# quectel_mc60_breakout.net
KiCad netlist of a schematic drawn in Altium Designer
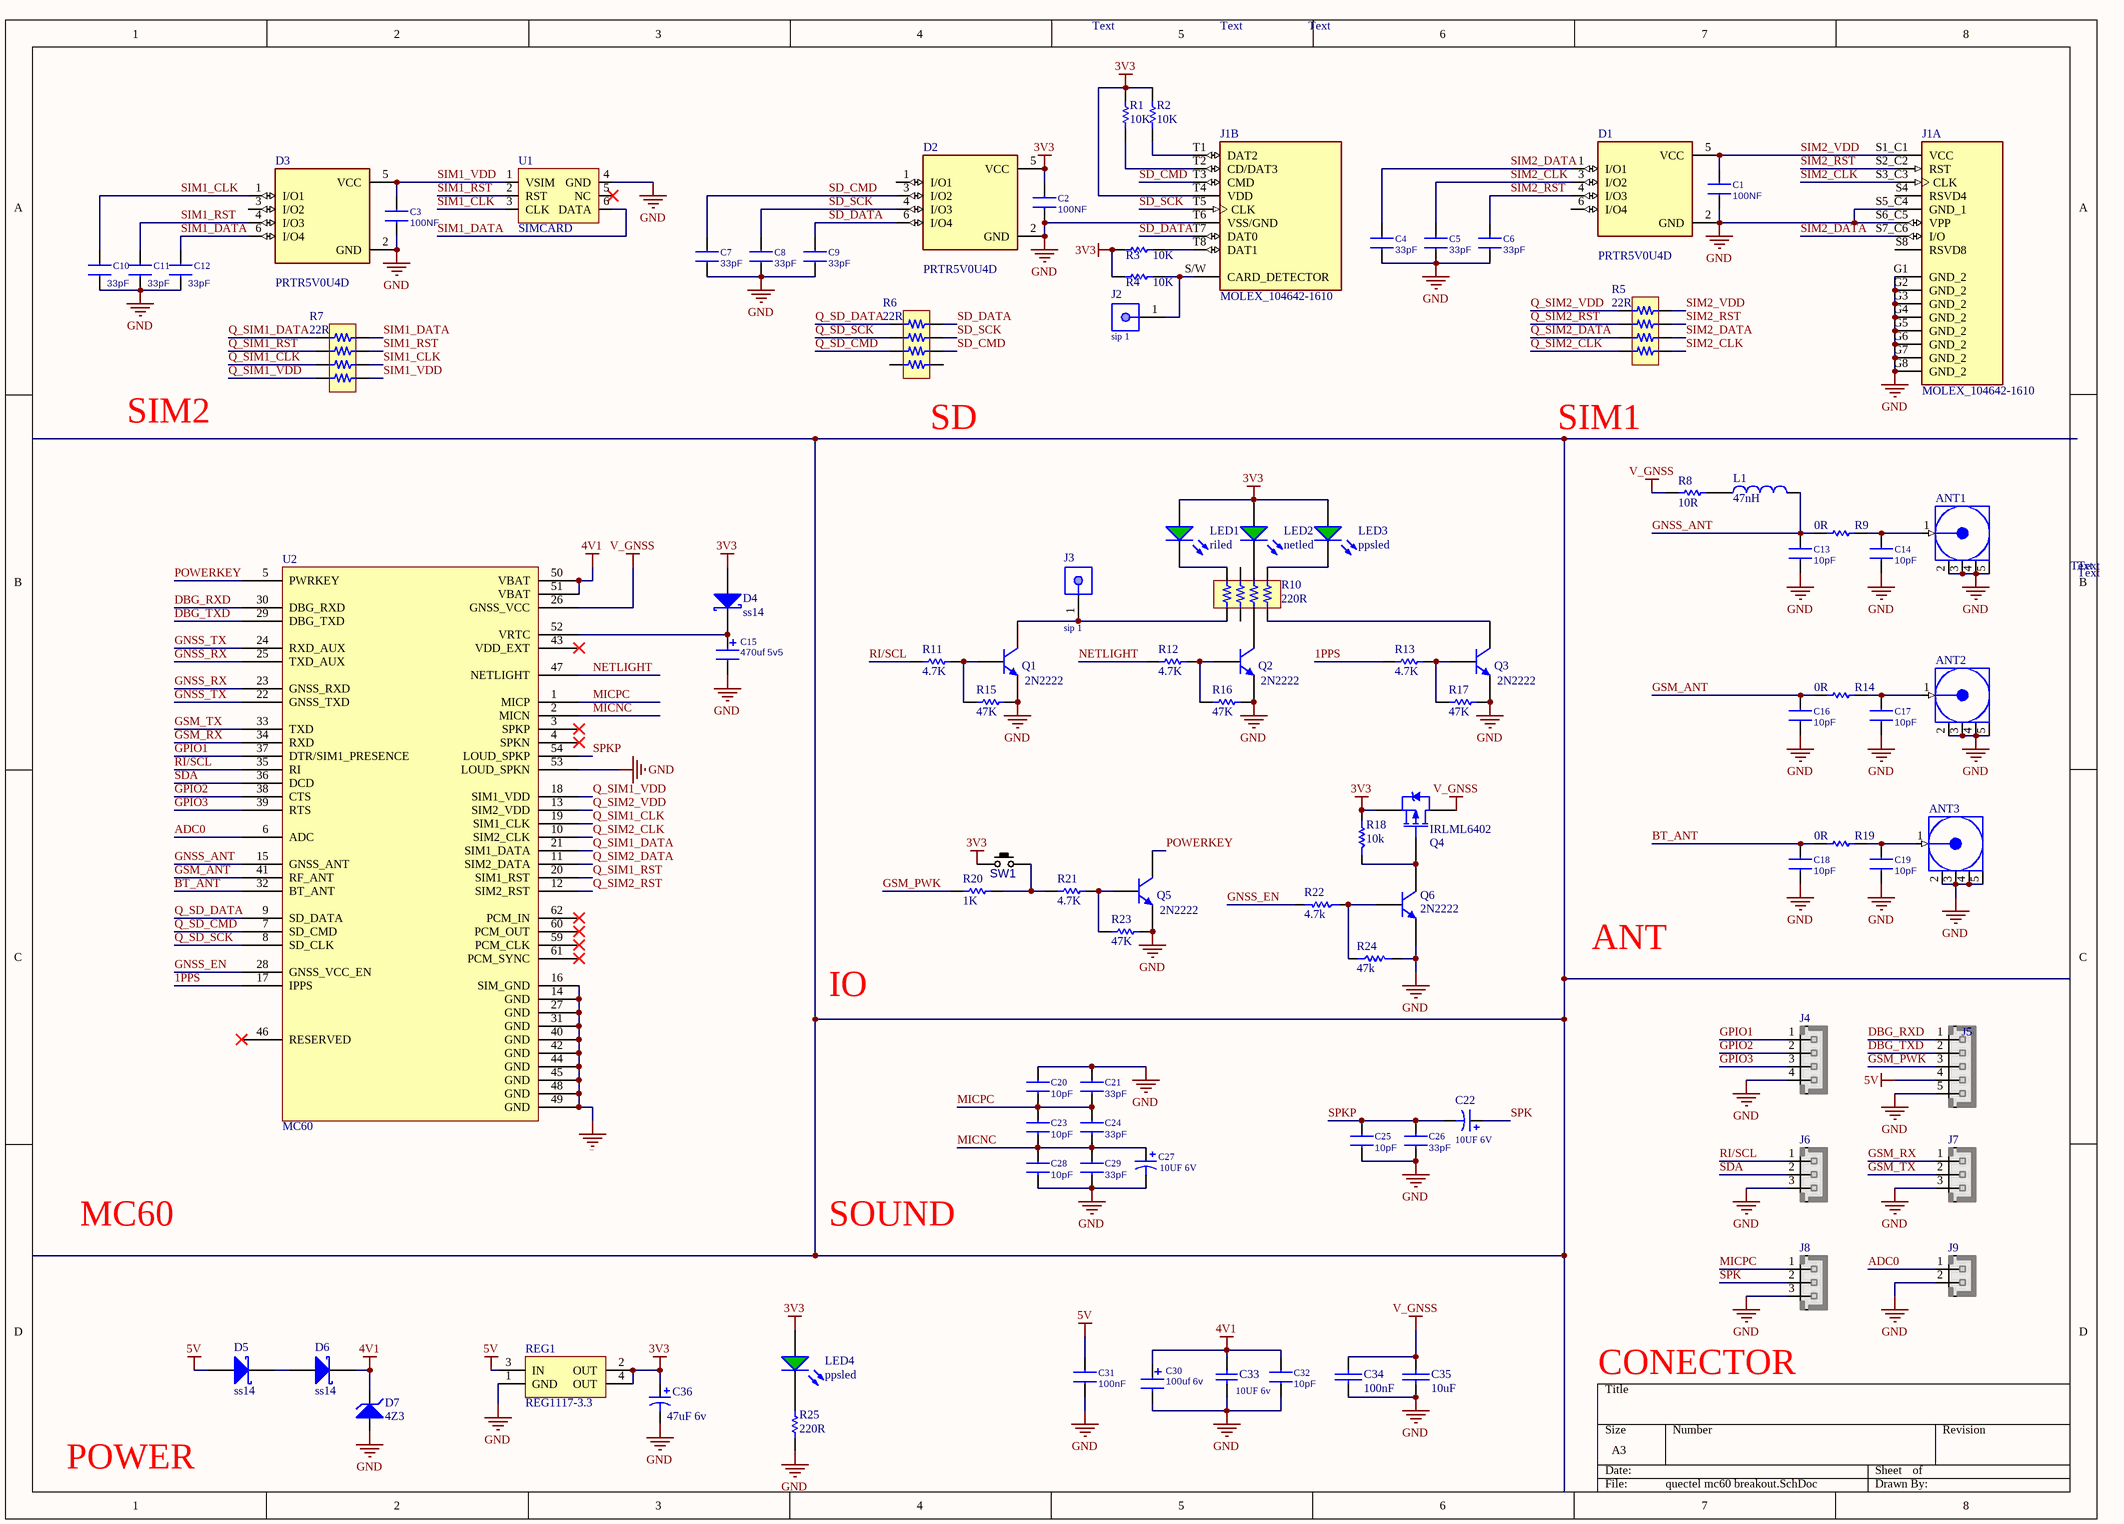
[diagram p0: quectel mc60 breakout.SchDoc]

(export (version "E")
  (design (tool "Eeschema 10.0.6"))
  (components
    (comp (ref "ANT1")
      (value "WR-SMA PCB Plug")
      (footprint "SMA-RA-6")
      (description "WR-SMA PCB Plug, THT, Right Angle")
      (fields (field (name "PART NUMBER") "60313002124523") (field (name "PUBLISHER") "Wurth Elektronik"))
      (libsource (lib "SMA") (part "WR-SMA PCB Plug"))
    )
    (comp (ref "ANT2")
      (value "WR-SMA PCB Plug")
      (footprint "SMA-RA-6")
      (description "WR-SMA PCB Plug, THT, Right Angle")
      (fields (field (name "PART NUMBER") "60313002124523") (field (name "PUBLISHER") "Wurth Elektronik"))
      (libsource (lib "SMA") (part "WR-SMA PCB Plug"))
    )
    (comp (ref "ANT3")
      (value "WR-SMA PCB Plug")
      (footprint "SMA-RA-6")
      (description "WR-SMA PCB Plug, THT, Right Angle")
      (fields (field (name "PART NUMBER") "60313002124523") (field (name "PUBLISHER") "Wurth Elektronik"))
      (libsource (lib "SMA") (part "WR-SMA PCB Plug"))
    )
    (comp (ref "C1")
      (value "100NF")
      (footprint "C0805E")
      (description "Capacitor")
      (libsource (lib "My_LIB") (part "Cap 1206"))
    )
    (comp (ref "C2")
      (value "100NF")
      (footprint "C0805E")
      (description "Capacitor")
      (libsource (lib "My_LIB") (part "Cap 1206"))
    )
    (comp (ref "C3")
      (value "100NF")
      (footprint "C0805E")
      (description "Capacitor")
      (libsource (lib "My_LIB") (part "Cap 1206"))
    )
    (comp (ref "C4")
      (value "33pF")
      (footprint "C0805E")
      (description "Capacitor")
      (libsource (lib "My_LIB") (part "Cap 1206"))
    )
    (comp (ref "C5")
      (value "33pF")
      (footprint "C0805E")
      (description "Capacitor")
      (libsource (lib "My_LIB") (part "Cap 1206"))
    )
    (comp (ref "C6")
      (value "33pF")
      (footprint "C0805E")
      (description "Capacitor")
      (libsource (lib "My_LIB") (part "Cap 1206"))
    )
    (comp (ref "C7")
      (value "33pF")
      (footprint "C0805E")
      (description "Capacitor")
      (libsource (lib "My_LIB") (part "Cap 1206"))
    )
    (comp (ref "C8")
      (value "33pF")
      (footprint "C0805E")
      (description "Capacitor")
      (libsource (lib "My_LIB") (part "Cap 1206"))
    )
    (comp (ref "C9")
      (value "33pF")
      (footprint "C0805E")
      (description "Capacitor")
      (libsource (lib "My_LIB") (part "Cap 1206"))
    )
    (comp (ref "C10")
      (value "33pF")
      (footprint "C0805E")
      (description "Capacitor")
      (libsource (lib "My_LIB") (part "Cap 1206"))
    )
    (comp (ref "C11")
      (value "33pF")
      (footprint "C0805E")
      (description "Capacitor")
      (libsource (lib "My_LIB") (part "Cap 1206"))
    )
    (comp (ref "C12")
      (value "33pF")
      (footprint "C0805E")
      (description "Capacitor")
      (libsource (lib "My_LIB") (part "Cap 1206"))
    )
    (comp (ref "C13")
      (value "10pF")
      (footprint "C0805E")
      (description "Capacitor")
      (libsource (lib "My_LIB") (part "Cap 1206"))
    )
    (comp (ref "C14")
      (value "10pF")
      (footprint "C0805E")
      (description "Capacitor")
      (libsource (lib "My_LIB") (part "Cap 1206"))
    )
    (comp (ref "C15")
      (value "470uf 5v5")
      (footprint "EEC S0HD473V")
      (description "Capacitor")
      (libsource (lib "My_LIB") (part "CPM3528"))
    )
    (comp (ref "C16")
      (value "10pF")
      (footprint "C0805E")
      (description "Capacitor")
      (libsource (lib "My_LIB") (part "Cap 1206"))
    )
    (comp (ref "C17")
      (value "10pF")
      (footprint "C0805E")
      (description "Capacitor")
      (libsource (lib "My_LIB") (part "Cap 1206"))
    )
    (comp (ref "C18")
      (value "10pF")
      (footprint "C0805E")
      (description "Capacitor")
      (libsource (lib "My_LIB") (part "Cap 1206"))
    )
    (comp (ref "C19")
      (value "10pF")
      (footprint "C0805E")
      (description "Capacitor")
      (libsource (lib "My_LIB") (part "Cap 1206"))
    )
    (comp (ref "C20")
      (value "10pF")
      (footprint "C0805E")
      (description "Capacitor")
      (libsource (lib "My_LIB") (part "Cap 1206"))
    )
    (comp (ref "C21")
      (value "33pF")
      (footprint "C0805E")
      (description "Capacitor")
      (libsource (lib "My_LIB") (part "Cap 1206"))
    )
    (comp (ref "C22")
      (value "10UF 6V")
      (footprint "C_TN_3216 (A)")
      (description "CAPASITOR ELECTRICAL DIP SMALL PACKAGE")
      (fields (field (name "PUBLISHER") "Altium Limited"))
      (libsource (lib "Integrated_Library_1") (part "CAP ELECTRICAL"))
    )
    (comp (ref "C23")
      (value "10pF")
      (footprint "C0805E")
      (description "Capacitor")
      (libsource (lib "My_LIB") (part "Cap 1206"))
    )
    (comp (ref "C24")
      (value "33pF")
      (footprint "C0805E")
      (description "Capacitor")
      (libsource (lib "My_LIB") (part "Cap 1206"))
    )
    (comp (ref "C25")
      (value "10pF")
      (footprint "C0805E")
      (description "Capacitor")
      (libsource (lib "My_LIB") (part "Cap 1206"))
    )
    (comp (ref "C26")
      (value "33pF")
      (footprint "C0805E")
      (description "Capacitor")
      (libsource (lib "My_LIB") (part "Cap 1206"))
    )
    (comp (ref "C27")
      (value "10UF 6V")
      (footprint "C_TN_3216 (A)")
      (description "CAPASITOR ELECTRICAL DIP SMALL PACKAGE")
      (fields (field (name "PUBLISHER") "Altium Limited"))
      (libsource (lib "Integrated_Library_1") (part "CAP ELECTRICAL"))
    )
    (comp (ref "C28")
      (value "10pF")
      (footprint "C0805E")
      (description "Capacitor")
      (libsource (lib "My_LIB") (part "Cap 1206"))
    )
    (comp (ref "C29")
      (value "33pF")
      (footprint "C0805E")
      (description "Capacitor")
      (libsource (lib "My_LIB") (part "Cap 1206"))
    )
    (comp (ref "C30")
      (value "100uf 6v")
      (footprint "C_TN_7343 (D)")
      (description "Capacitor")
      (libsource (lib "My_LIB") (part "CPM3528"))
    )
    (comp (ref "C31")
      (value "100nF")
      (footprint "C0805E")
      (description "Capacitor")
      (libsource (lib "My_LIB") (part "Cap 1206"))
    )
    (comp (ref "C32")
      (value "10pF")
      (footprint "C0805E")
      (description "Capacitor")
      (libsource (lib "My_LIB") (part "Cap 1206"))
    )
    (comp (ref "C33")
      (value "10UF 6v")
      (footprint "C_TN_3216 (A)")
      (description "Capacitor")
      (fields (field (name "PUBLISHER") "Altium Limited"))
      (libsource (lib "Miscellaneous Devices") (part "Cap"))
    )
    (comp (ref "C34")
      (value "100nF")
      (footprint "C0805E")
      (description "Bipolar Capacitor")
      (fields (field (name "VOLTAGE") "100V") (field (name "DESIGNER") "Saeid Jorablo"))
      (libsource (lib "My Library") (part "Cap-Bipolar"))
    )
    (comp (ref "C35")
      (value "10uF")
      (footprint "C_TN_3216 (A)")
      (description "Bipolar Capacitor")
      (fields (field (name "VOLTAGE") "100V") (field (name "DESIGNER") "Saeid Jorablo"))
      (libsource (lib "My Library") (part "Cap-Bipolar"))
    )
    (comp (ref "C36")
      (value "47uF 6v")
      (footprint "C_TN_3528 (B)")
      (description "Polarized Capacitor (Radial)")
      (fields (field (name "PUBLISHER") "Altium Limited"))
      (libsource (lib "Miscellaneous Devices") (part "Cap Pol1"))
    )
    (comp (ref "D1")
      (value "PRTR5V0U4D")
      (footprint "PRTR5V0U4D")
      (libsource (lib "PRTR5V0U4D") (part "PRTR5V0U4D"))
    )
    (comp (ref "D2")
      (value "PRTR5V0U4D")
      (footprint "PRTR5V0U4D")
      (libsource (lib "PRTR5V0U4D") (part "PRTR5V0U4D"))
    )
    (comp (ref "D3")
      (value "PRTR5V0U4D")
      (footprint "PRTR5V0U4D")
      (libsource (lib "PRTR5V0U4D") (part "PRTR5V0U4D"))
    )
    (comp (ref "D4")
      (value "ss14")
      (footprint "SMA")
      (description "Silicon Schottky Diode for High-Speed Switching")
      (fields (field (name "PUBLISHER") "Altium Limited"))
      (libsource (lib "diode") (part "Schottky"))
    )
    (comp (ref "D5")
      (value "ss14")
      (footprint "SMA")
      (description "Silicon Schottky Diode for High-Speed Switching")
      (fields (field (name "PUBLISHER") "Altium Limited"))
      (libsource (lib "diode") (part "Schottky"))
    )
    (comp (ref "D6")
      (value "ss14")
      (footprint "SMA")
      (description "Silicon Schottky Diode for High-Speed Switching")
      (fields (field (name "PUBLISHER") "Altium Limited"))
      (libsource (lib "diode") (part "Schottky"))
    )
    (comp (ref "D7")
      (value "4Z3")
      (footprint "SOD80")
      (description "Zener Diode")
      (fields (field (name "PUBLISHER") "Altium Limited"))
      (libsource (lib "My_LIB") (part "D Zener"))
    )
    (comp (ref "J1")
      (value "MOLEX_104642-1610")
      (footprint "MOLEX_104642-1610")
      (fields (field (name "MF") "Molex") (field (name "MP") "104642-1610"))
      (libsource (lib "SIM") (part "MOLEX_104642-1610"))
    )
    (comp (ref "J2")
      (value "sip 1")
      (footprint "1_SIP")
      (description "WR-PHD Pin Header, THT, pitch 2.54mm, Single Row, Vertical, 1pin")
      (fields (field (name "PART NUMBER") "61300111121") (field (name "PUBLISHER") "Wurth Elektronik"))
      (libsource (lib "sip m") (part "sip 1"))
    )
    (comp (ref "J3")
      (value "sip 1")
      (footprint "1_SIP")
      (description "WR-PHD Pin Header, THT, pitch 2.54mm, Single Row, Vertical, 1pin")
      (fields (field (name "PART NUMBER") "61300111121") (field (name "PUBLISHER") "Wurth Elektronik"))
      (libsource (lib "sip m") (part "sip 1"))
    )
    (comp (ref "J4")
      (value "HHDR_4")
      (footprint "XH_4")
      (description "JST-XH pitch: 2.5mm")
      (libsource (lib "xh-xhr-wf-hhdr-hh6r") (part "XH_4"))
    )
    (comp (ref "J5")
      (value "XH_5")
      (footprint "XH_5")
      (description "JST-XH pitch: 2.5mm")
      (fields (field (name "MANF") "JST") (field (name "MANF_P#") "JST-B5B-XHA"))
      (libsource (lib "xh-xhr-wf-hhdr-hh6r") (part "XH_5"))
    )
    (comp (ref "J6")
      (value "HHDR_3")
      (footprint "XH_3")
      (description "JST-XH pitch: 2.5mm")
      (libsource (lib "xh-xhr-wf-hhdr-hh6r") (part "XH_3"))
    )
    (comp (ref "J7")
      (value "HHDR_3")
      (footprint "XH_3")
      (description "JST-XH pitch: 2.5mm")
      (libsource (lib "xh-xhr-wf-hhdr-hh6r") (part "XH_3"))
    )
    (comp (ref "J8")
      (value "HHDR_3")
      (footprint "XH_3")
      (description "JST-XH pitch: 2.5mm")
      (libsource (lib "xh-xhr-wf-hhdr-hh6r") (part "XH_3"))
    )
    (comp (ref "J9")
      (value "HHDR_2")
      (footprint "XH_2")
      (description "JST-XH pitch: 2.5mm")
      (libsource (lib "xh-xhr-wf-hhdr-hh6r") (part "XH_2"))
    )
    (comp (ref "L1")
      (value "47nH")
      (footprint "L0805E")
      (description "SMT Power Inductor; Size 6.3�6.3�3.0mm, �20% Tolerance, 1uH, 3.4A")
      (fields (field (name "PUBLISHER") "Altium Limited"))
      (libsource (lib "EPCOS Inductor") (part "B82462G4102M000"))
    )
    (comp (ref "LED1") (value "riled") (footprint "LED1206RED") (libsource (lib "OTHER") (part "LED3mm")))
    (comp (ref "LED2") (value "netled") (footprint "LED1206RED") (libsource (lib "OTHER") (part "LED3mm")))
    (comp (ref "LED3") (value "ppsled") (footprint "LED1206RED") (libsource (lib "OTHER") (part "LED3mm")))
    (comp (ref "LED4") (value "ppsled") (footprint "LED1206RED") (libsource (lib "OTHER") (part "LED3mm")))
    (comp (ref "Q1")
      (value "2N2222")
      (footprint "SOT-23A")
      (description "NPN 2N2222 SMD TRANSISTOR")
      (fields (field (name "PUBLISHER") "Altium Limited"))
      (libsource (lib "Integrated_Library_1") (part "BC547 SMD"))
    )
    (comp (ref "Q2")
      (value "2N2222")
      (footprint "SOT-23A")
      (description "NPN 2N2222 SMD TRANSISTOR")
      (fields (field (name "PUBLISHER") "Altium Limited"))
      (libsource (lib "Integrated_Library_1") (part "BC547 SMD"))
    )
    (comp (ref "Q3")
      (value "2N2222")
      (footprint "SOT-23A")
      (description "NPN 2N2222 SMD TRANSISTOR")
      (fields (field (name "PUBLISHER") "Altium Limited"))
      (libsource (lib "Integrated_Library_1") (part "BC547 SMD"))
    )
    (comp (ref "Q4")
      (value "IRLML6402")
      (footprint "SOT-23A")
      (description "HEXFET Power MOSFET")
      (fields (field (name "PUBLISHER") "Altium Limited"))
      (libsource (lib "IR Discrete MOSFET - Power") (part "IRLML6401"))
    )
    (comp (ref "Q5")
      (value "2N2222")
      (footprint "SOT-23A")
      (description "NPN2N2222 SMD TRANSISTOR")
      (fields (field (name "PUBLISHER") "Altium Limited"))
      (libsource (lib "Integrated_Library_1") (part "BC547 SMD"))
    )
    (comp (ref "Q6")
      (value "2N2222")
      (footprint "SOT-23A")
      (description "NPN2N2222 SMD TRANSISTOR")
      (fields (field (name "PUBLISHER") "Altium Limited"))
      (libsource (lib "Philips Discrete BJT - Low Power") (part "PMBT3904"))
    )
    (comp (ref "R1")
      (value "10K")
      (footprint "R0805E")
      (description "Resistor")
      (fields (field (name "PUBLISHER") "Altium Limited"))
      (libsource (lib "Miscellaneous Devices") (part "Res1"))
    )
    (comp (ref "R2")
      (value "10K")
      (footprint "R0805E")
      (description "Resistor")
      (fields (field (name "PUBLISHER") "Altium Limited"))
      (libsource (lib "Miscellaneous Devices") (part "Res1"))
    )
    (comp (ref "R3")
      (value "10K")
      (footprint "R0805E")
      (description "Resistor")
      (fields (field (name "PUBLISHER") "Altium Limited"))
      (libsource (lib "Miscellaneous Devices") (part "Res1"))
    )
    (comp (ref "R4")
      (value "10K")
      (footprint "R0805E")
      (description "Resistor")
      (fields (field (name "PUBLISHER") "Altium Limited"))
      (libsource (lib "Miscellaneous Devices") (part "Res1"))
    )
    (comp (ref "R5")
      (value "22R")
      (footprint "RESNET 1206-8")
      (libsource (lib "RESISTOR ARRAY SMD 8") (part "Resistor Array 4"))
    )
    (comp (ref "R6")
      (value "22R")
      (footprint "RESNET 1206-8")
      (libsource (lib "RESISTOR ARRAY SMD 8") (part "Resistor Array 4"))
    )
    (comp (ref "R7")
      (value "22R")
      (footprint "RESNET 1206-8")
      (libsource (lib "RESISTOR ARRAY SMD 8") (part "Resistor Array 4"))
    )
    (comp (ref "R8")
      (value "10R")
      (footprint "R0805E")
      (description "Resistor")
      (fields (field (name "PUBLISHER") "Altium Limited"))
      (libsource (lib "Miscellaneous Devices") (part "Res1"))
    )
    (comp (ref "R9")
      (value "0R")
      (footprint "R0805E")
      (description "Resistor")
      (fields (field (name "PUBLISHER") "Altium Limited"))
      (libsource (lib "Miscellaneous Devices") (part "Res1"))
    )
    (comp (ref "R10")
      (value "220R")
      (footprint "RESNET 1206-8")
      (libsource (lib "") (part "Resistor Array 4_1"))
    )
    (comp (ref "R11")
      (value "4.7K")
      (footprint "R0805E")
      (description "Resistor")
      (fields (field (name "PUBLISHER") "Altium Limited"))
      (libsource (lib "Miscellaneous Devices") (part "Res1"))
    )
    (comp (ref "R12")
      (value "4.7K")
      (footprint "R0805E")
      (description "Resistor")
      (fields (field (name "PUBLISHER") "Altium Limited"))
      (libsource (lib "Miscellaneous Devices") (part "Res1"))
    )
    (comp (ref "R13")
      (value "4.7K")
      (footprint "R0805E")
      (description "Resistor")
      (fields (field (name "PUBLISHER") "Altium Limited"))
      (libsource (lib "Miscellaneous Devices") (part "Res1"))
    )
    (comp (ref "R14")
      (value "0R")
      (footprint "R0805E")
      (description "Resistor")
      (fields (field (name "PUBLISHER") "Altium Limited"))
      (libsource (lib "Miscellaneous Devices") (part "Res1"))
    )
    (comp (ref "R15")
      (value "47K")
      (footprint "R0805E")
      (description "Resistor")
      (fields (field (name "PUBLISHER") "Altium Limited"))
      (libsource (lib "Miscellaneous Devices") (part "Res1"))
    )
    (comp (ref "R16")
      (value "47K")
      (footprint "R0805E")
      (description "Resistor")
      (fields (field (name "PUBLISHER") "Altium Limited"))
      (libsource (lib "Miscellaneous Devices") (part "Res1"))
    )
    (comp (ref "R17")
      (value "47K")
      (footprint "R0805E")
      (description "Resistor")
      (fields (field (name "PUBLISHER") "Altium Limited"))
      (libsource (lib "Miscellaneous Devices") (part "Res1"))
    )
    (comp (ref "R18")
      (value "10k")
      (footprint "R0805E")
      (description "Resistor")
      (libsource (lib "My Library") (part "Resistor"))
    )
    (comp (ref "R19")
      (value "0R")
      (footprint "R0805E")
      (description "Resistor")
      (fields (field (name "PUBLISHER") "Altium Limited"))
      (libsource (lib "Miscellaneous Devices") (part "Res1"))
    )
    (comp (ref "R20")
      (value "1K")
      (footprint "R0805E")
      (description "Resistor")
      (fields (field (name "PUBLISHER") "Altium Limited"))
      (libsource (lib "Miscellaneous Devices") (part "Res1"))
    )
    (comp (ref "R21")
      (value "4.7K")
      (footprint "R0805E")
      (description "Resistor")
      (fields (field (name "PUBLISHER") "Altium Limited"))
      (libsource (lib "Miscellaneous Devices") (part "Res1"))
    )
    (comp (ref "R22")
      (value "4.7k")
      (footprint "R0805E")
      (description "Resistor")
      (libsource (lib "My Library") (part "Resistor"))
    )
    (comp (ref "R23")
      (value "47K")
      (footprint "R0805E")
      (description "Resistor")
      (fields (field (name "PUBLISHER") "Altium Limited"))
      (libsource (lib "Miscellaneous Devices") (part "Res1"))
    )
    (comp (ref "R24")
      (value "47k")
      (footprint "R0805E")
      (description "Resistor")
      (libsource (lib "My Library") (part "Resistor"))
    )
    (comp (ref "R25")
      (value "220R")
      (footprint "R0805E")
      (description "Resistor")
      (fields (field (name "PUBLISHER") "Altium Limited"))
      (libsource (lib "Miscellaneous Devices") (part "Res1"))
    )
    (comp (ref "REG1")
      (value "REG1117-3.3")
      (footprint "SOT223_L")
      (description "800mA and 1A Low Dropout Positive Regulator 2.85V, 3.3V, 5V, and Adjustable")
      (fields (field (name "PUBLISHER") "Altium Limited"))
      (libsource (lib "BB Power Mgt Voltage Regulator") (part "REG1117-3.3"))
    )
    (comp (ref "SW1")
      (value "PUSHBUTTON")
      (footprint "SWPBS_SPST_6X3X5")
      (description "SWITCH, PUSH BUTTON, TACTILE, SMD, SPST, 6X3.5X4.3mm")
      (fields (field (name "MANF") "Panasonic") (field (name "MANF_P#") "EVQ-PNF04M"))
      (libsource (lib "switch_tact_PUSHB") (part "SWPBS_SPST_6X3X4"))
    )
    (comp (ref "U1")
      (value "SIMCARD")
      (footprint "DESIRE 626")
      (libsource (lib "SIMCARD") (part "SIMCARD 6PIN"))
    )
    (comp (ref "U2") (value "MC60") (footprint "MC60") (libsource (lib "GSM") (part "MC60")))
  )
  (nets
    (net (code "1") (name "/1PPS") (class "Default")
      (node (ref "R13") (pin "1") (pinfunction "1_1") (pintype "passive"))
      (node (ref "U2") (pin "17") (pinfunction "IPPS_17") (pintype "passive"))
    )
    (net (code "2") (name "/ADC0") (class "Default")
      (node (ref "J9") (pin "1") (pinfunction "1_1") (pintype "passive"))
      (node (ref "U2") (pin "6") (pinfunction "ADC_6") (pintype "passive"))
    )
    (net (code "3") (name "/BT_ANT") (class "Default")
      (node (ref "C18") (pin "1") (pintype "passive"))
      (node (ref "R19") (pin "1") (pinfunction "1_1") (pintype "passive"))
      (node (ref "U2") (pin "32") (pinfunction "BT_ANT_32") (pintype "passive"))
    )
    (net (code "4") (name "/DBG_RXD") (class "Default")
      (node (ref "J5") (pin "1") (pinfunction "1_1") (pintype "passive"))
      (node (ref "U2") (pin "30") (pinfunction "DBG_RXD_30") (pintype "passive"))
    )
    (net (code "5") (name "/DBG_TXD") (class "Default")
      (node (ref "J5") (pin "2") (pinfunction "2_2") (pintype "passive"))
      (node (ref "U2") (pin "29") (pinfunction "DBG_TXD_29") (pintype "passive"))
    )
    (net (code "6") (name "/GNSS_ANT") (class "Default")
      (node (ref "C13") (pin "1") (pintype "passive"))
      (node (ref "L1") (pin "2") (pinfunction "2_2") (pintype "passive"))
      (node (ref "R9") (pin "1") (pinfunction "1_1") (pintype "passive"))
      (node (ref "U2") (pin "15") (pinfunction "GNSS_ANT_15") (pintype "passive"))
    )
    (net (code "7") (name "/GNSS_EN") (class "Default")
      (node (ref "R22") (pin "2") (pinfunction "2_2") (pintype "passive"))
      (node (ref "U2") (pin "28") (pinfunction "GNSS_VCC_EN_28") (pintype "passive"))
    )
    (net (code "8") (name "/GNSS_RX") (class "Default")
      (node (ref "U2") (pin "23") (pinfunction "GNSS_RXD_23") (pintype "passive"))
      (node (ref "U2") (pin "25") (pinfunction "TXD_AUX_25") (pintype "passive"))
    )
    (net (code "9") (name "/GNSS_TX") (class "Default")
      (node (ref "U2") (pin "22") (pinfunction "GNSS_TXD_22") (pintype "passive"))
      (node (ref "U2") (pin "24") (pinfunction "RXD_AUX_24") (pintype "passive"))
    )
    (net (code "10") (name "/GPIO1") (class "Default")
      (node (ref "J4") (pin "1") (pinfunction "1_1") (pintype "passive"))
      (node (ref "U2") (pin "37") (pinfunction "DTR/SIM1_PRESENCE_37") (pintype "passive"))
    )
    (net (code "11") (name "/GPIO2") (class "Default")
      (node (ref "J4") (pin "2") (pinfunction "2_2") (pintype "passive"))
      (node (ref "U2") (pin "38") (pinfunction "CTS_38") (pintype "passive"))
    )
    (net (code "12") (name "/GPIO3") (class "Default")
      (node (ref "J4") (pin "3") (pinfunction "3_3") (pintype "passive"))
      (node (ref "U2") (pin "39") (pinfunction "RTS_39") (pintype "passive"))
    )
    (net (code "13") (name "/GSM_ANT") (class "Default")
      (node (ref "C16") (pin "1") (pintype "passive"))
      (node (ref "R14") (pin "1") (pinfunction "1_1") (pintype "passive"))
      (node (ref "U2") (pin "41") (pinfunction "RF_ANT_41") (pintype "passive"))
    )
    (net (code "14") (name "/GSM_PWK") (class "Default")
      (node (ref "J5") (pin "3") (pinfunction "3_3") (pintype "passive"))
      (node (ref "R20") (pin "1") (pinfunction "1_1") (pintype "passive"))
    )
    (net (code "15") (name "/GSM_RX") (class "Default")
      (node (ref "J7") (pin "1") (pinfunction "1_1") (pintype "passive"))
      (node (ref "U2") (pin "34") (pinfunction "RXD_34") (pintype "passive"))
    )
    (net (code "16") (name "/GSM_TX") (class "Default")
      (node (ref "J7") (pin "2") (pinfunction "2_2") (pintype "passive"))
      (node (ref "U2") (pin "33") (pinfunction "TXD_33") (pintype "passive"))
    )
    (net (code "17") (name "/MICNC") (class "Default")
      (node (ref "C23") (pin "2") (pintype "passive"))
      (node (ref "C24") (pin "2") (pintype "passive"))
      (node (ref "C27") (pin "1") (pinfunction "1_1") (pintype "passive"))
      (node (ref "C28") (pin "1") (pintype "passive"))
      (node (ref "C29") (pin "1") (pintype "passive"))
      (node (ref "U2") (pin "2") (pinfunction "MICN_2") (pintype "passive"))
    )
    (net (code "18") (name "/MICPC") (class "Default")
      (node (ref "C20") (pin "2") (pintype "passive"))
      (node (ref "C21") (pin "2") (pintype "passive"))
      (node (ref "C23") (pin "1") (pintype "passive"))
      (node (ref "C24") (pin "1") (pintype "passive"))
      (node (ref "J8") (pin "1") (pinfunction "1_1") (pintype "passive"))
      (node (ref "U2") (pin "1") (pinfunction "MICP_1") (pintype "passive"))
    )
    (net (code "19") (name "/NETLIGHT") (class "Default")
      (node (ref "R12") (pin "1") (pinfunction "1_1") (pintype "passive"))
      (node (ref "U2") (pin "47") (pinfunction "NETLIGHT_47") (pintype "passive"))
    )
    (net (code "20") (name "/POWERKEY") (class "Default")
      (node (ref "Q5") (pin "3") (pinfunction "C_3") (pintype "passive"))
      (node (ref "U2") (pin "5") (pinfunction "PWRKEY_5") (pintype "passive"))
    )
    (net (code "21") (name "/Q_SD_CMD") (class "Default")
      (node (ref "R6") (pin "3") (pinfunction "3_3") (pintype "passive"))
      (node (ref "U2") (pin "7") (pinfunction "SD_CMD_7") (pintype "passive"))
    )
    (net (code "22") (name "/Q_SD_DATA") (class "Default")
      (node (ref "R6") (pin "1") (pinfunction "1_1") (pintype "passive"))
      (node (ref "U2") (pin "9") (pinfunction "SD_DATA_9") (pintype "passive"))
    )
    (net (code "23") (name "/Q_SD_SCK") (class "Default")
      (node (ref "R6") (pin "2") (pinfunction "2_2") (pintype "passive"))
      (node (ref "U2") (pin "8") (pinfunction "SD_CLK_8") (pintype "passive"))
    )
    (net (code "24") (name "/Q_SIM1_CLK") (class "Default")
      (node (ref "R7") (pin "3") (pinfunction "3_3") (pintype "passive"))
      (node (ref "U2") (pin "19") (pinfunction "SIM1_CLK_19") (pintype "passive"))
    )
    (net (code "25") (name "/Q_SIM1_DATA") (class "Default")
      (node (ref "R7") (pin "1") (pinfunction "1_1") (pintype "passive"))
      (node (ref "U2") (pin "21") (pinfunction "SIM1_DATA_21") (pintype "passive"))
    )
    (net (code "26") (name "/Q_SIM1_RST") (class "Default")
      (node (ref "R7") (pin "2") (pinfunction "2_2") (pintype "passive"))
      (node (ref "U2") (pin "20") (pinfunction "SIM1_RST_20") (pintype "passive"))
    )
    (net (code "27") (name "/Q_SIM1_VDD") (class "Default")
      (node (ref "R7") (pin "4") (pinfunction "4_4") (pintype "passive"))
      (node (ref "U2") (pin "18") (pinfunction "SIM1_VDD_18") (pintype "passive"))
    )
    (net (code "28") (name "/Q_SIM2_CLK") (class "Default")
      (node (ref "R5") (pin "4") (pinfunction "4_4") (pintype "passive"))
      (node (ref "U2") (pin "10") (pinfunction "SIM2_CLK_10") (pintype "passive"))
    )
    (net (code "29") (name "/Q_SIM2_DATA") (class "Default")
      (node (ref "R5") (pin "3") (pinfunction "3_3") (pintype "passive"))
      (node (ref "U2") (pin "11") (pinfunction "SIM2_DATA_11") (pintype "passive"))
    )
    (net (code "30") (name "/Q_SIM2_RST") (class "Default")
      (node (ref "R5") (pin "2") (pinfunction "2_2") (pintype "passive"))
      (node (ref "U2") (pin "12") (pinfunction "SIM2_RST_12") (pintype "passive"))
    )
    (net (code "31") (name "/Q_SIM2_VDD") (class "Default")
      (node (ref "R5") (pin "1") (pinfunction "1_1") (pintype "passive"))
      (node (ref "U2") (pin "13") (pinfunction "SIM2_VDD_13") (pintype "passive"))
    )
    (net (code "32") (name "/RI{slash}SCL") (class "Default")
      (node (ref "J6") (pin "1") (pinfunction "1_1") (pintype "passive"))
      (node (ref "R11") (pin "1") (pinfunction "1_1") (pintype "passive"))
      (node (ref "U2") (pin "35") (pinfunction "RI_35") (pintype "passive"))
    )
    (net (code "33") (name "/SDA") (class "Default")
      (node (ref "J6") (pin "2") (pinfunction "2_2") (pintype "passive"))
      (node (ref "U2") (pin "36") (pinfunction "DCD_36") (pintype "passive"))
    )
    (net (code "34") (name "/SD_CMD") (class "Default")
      (node (ref "C7") (pin "1") (pintype "passive"))
      (node (ref "D2") (pin "3") (pinfunction "I/O2_3") (pintype "bidirectional"))
      (node (ref "J1") (pin "T3") (pinfunction "CMD_T3") (pintype "bidirectional"))
      (node (ref "R6") (pin "6") (pinfunction "6_6") (pintype "passive"))
    )
    (net (code "35") (name "/SD_DATA") (class "Default")
      (node (ref "C9") (pin "1") (pintype "passive"))
      (node (ref "D2") (pin "6") (pinfunction "I/O4_6") (pintype "bidirectional"))
      (node (ref "J1") (pin "T7") (pinfunction "DAT0_T7") (pintype "bidirectional"))
      (node (ref "R6") (pin "8") (pinfunction "8_8") (pintype "passive"))
    )
    (net (code "36") (name "/SD_SCK") (class "Default")
      (node (ref "C8") (pin "1") (pintype "passive"))
      (node (ref "D2") (pin "4") (pinfunction "I/O3_4") (pintype "bidirectional"))
      (node (ref "J1") (pin "T5") (pinfunction "CLK_T5") (pintype "input"))
      (node (ref "R6") (pin "7") (pinfunction "7_7") (pintype "passive"))
    )
    (net (code "37") (name "/SIM1_CLK") (class "Default")
      (node (ref "C10") (pin "1") (pintype "passive"))
      (node (ref "D3") (pin "1") (pinfunction "I/O1_1") (pintype "bidirectional"))
      (node (ref "R7") (pin "6") (pinfunction "6_6") (pintype "passive"))
      (node (ref "U1") (pin "3") (pinfunction "CLK_3") (pintype "passive"))
    )
    (net (code "38") (name "/SIM1_DATA") (class "Default")
      (node (ref "C12") (pin "1") (pintype "passive"))
      (node (ref "D3") (pin "6") (pinfunction "I/O4_6") (pintype "bidirectional"))
      (node (ref "R7") (pin "8") (pinfunction "8_8") (pintype "passive"))
      (node (ref "U1") (pin "6") (pinfunction "DATA_6") (pintype "passive"))
    )
    (net (code "39") (name "/SIM1_RST") (class "Default")
      (node (ref "C11") (pin "1") (pintype "passive"))
      (node (ref "D3") (pin "4") (pinfunction "I/O3_4") (pintype "bidirectional"))
      (node (ref "R7") (pin "7") (pinfunction "7_7") (pintype "passive"))
      (node (ref "U1") (pin "2") (pinfunction "RST_2") (pintype "passive"))
    )
    (net (code "40") (name "/SIM1_VDD") (class "Default")
      (node (ref "C3") (pin "1") (pintype "passive"))
      (node (ref "D3") (pin "5") (pinfunction "VCC_5") (pintype "power_in"))
      (node (ref "R7") (pin "5") (pinfunction "5_5") (pintype "passive"))
      (node (ref "U1") (pin "1") (pinfunction "VSIM_1") (pintype "passive"))
    )
    (net (code "41") (name "/SIM2_CLK") (class "Default")
      (node (ref "C5") (pin "1") (pintype "passive"))
      (node (ref "D1") (pin "3") (pinfunction "I/O2_3") (pintype "bidirectional"))
      (node (ref "J1") (pin "S3_C3") (pinfunction "CLK_S3_C3") (pintype "input"))
      (node (ref "R5") (pin "5") (pinfunction "5_5") (pintype "passive"))
    )
    (net (code "42") (name "/SIM2_DATA") (class "Default")
      (node (ref "C4") (pin "1") (pintype "passive"))
      (node (ref "D1") (pin "1") (pinfunction "I/O1_1") (pintype "bidirectional"))
      (node (ref "J1") (pin "S7_C6") (pinfunction "I/O_S7_C6") (pintype "bidirectional"))
      (node (ref "R5") (pin "6") (pinfunction "6_6") (pintype "passive"))
    )
    (net (code "43") (name "/SIM2_RST") (class "Default")
      (node (ref "C6") (pin "1") (pintype "passive"))
      (node (ref "D1") (pin "4") (pinfunction "I/O3_4") (pintype "bidirectional"))
      (node (ref "J1") (pin "S2_C2") (pinfunction "RST_S2_C2") (pintype "input"))
      (node (ref "R5") (pin "7") (pinfunction "7_7") (pintype "passive"))
    )
    (net (code "44") (name "/SIM2_VDD") (class "Default")
      (node (ref "C1") (pin "1") (pintype "passive"))
      (node (ref "D1") (pin "5") (pinfunction "VCC_5") (pintype "power_in"))
      (node (ref "J1") (pin "S1_C1") (pinfunction "VCC_S1_C1") (pintype "power_in"))
      (node (ref "R5") (pin "8") (pinfunction "8_8") (pintype "passive"))
    )
    (net (code "45") (name "/SPK") (class "Default")
      (node (ref "C22") (pin "1") (pinfunction "1_1") (pintype "passive"))
      (node (ref "J8") (pin "2") (pinfunction "2_2") (pintype "passive"))
    )
    (net (code "46") (name "/SPKP") (class "Default")
      (node (ref "C22") (pin "2") (pinfunction "2_2") (pintype "passive"))
      (node (ref "C25") (pin "1") (pintype "passive"))
      (node (ref "C26") (pin "1") (pintype "passive"))
      (node (ref "U2") (pin "54") (pinfunction "LOUD_SPKP_54") (pintype "passive"))
    )
    (net (code "47") (name "3V3") (class "Default")
      (node (ref "C2") (pin "1") (pintype "passive"))
      (node (ref "C36") (pin "1") (pinfunction "1_1") (pintype "passive"))
      (node (ref "D2") (pin "5") (pinfunction "VCC_5") (pintype "power_in"))
      (node (ref "D4") (pin "1") (pinfunction "A_1") (pintype "passive"))
      (node (ref "J1") (pin "T4") (pinfunction "VDD_T4") (pintype "power_in"))
      (node (ref "LED1") (pin "1") (pinfunction "A_1") (pintype "passive"))
      (node (ref "LED2") (pin "1") (pinfunction "A_1") (pintype "passive"))
      (node (ref "LED3") (pin "1") (pinfunction "A_1") (pintype "passive"))
      (node (ref "LED4") (pin "1") (pinfunction "A_1") (pintype "passive"))
      (node (ref "Q4") (pin "2") (pinfunction "S_2") (pintype "passive"))
      (node (ref "R1") (pin "2") (pinfunction "2_2") (pintype "passive"))
      (node (ref "R18") (pin "2") (pinfunction "2_2") (pintype "passive"))
      (node (ref "R2") (pin "2") (pinfunction "2_2") (pintype "passive"))
      (node (ref "R3") (pin "2") (pinfunction "2_2") (pintype "passive"))
      (node (ref "R4") (pin "2") (pinfunction "2_2") (pintype "passive"))
      (node (ref "REG1") (pin "2") (pinfunction "OUT_2") (pintype "power_in"))
      (node (ref "REG1") (pin "4") (pinfunction "OUT_4") (pintype "power_in"))
      (node (ref "SW1") (pin "1") (pinfunction "P1_1") (pintype "passive"))
    )
    (net (code "48") (name "4V1") (class "Default")
      (node (ref "C30") (pin "1") (pinfunction "1_1") (pintype "passive"))
      (node (ref "C32") (pin "2") (pintype "passive"))
      (node (ref "C33") (pin "1") (pinfunction "1_1") (pintype "passive"))
      (node (ref "D6") (pin "2") (pinfunction "K_2") (pintype "passive"))
      (node (ref "D7") (pin "2") (pinfunction "K_2") (pintype "passive"))
      (node (ref "U2") (pin "50") (pinfunction "VBAT_50") (pintype "passive"))
      (node (ref "U2") (pin "51") (pinfunction "VBAT_51") (pintype "passive"))
    )
    (net (code "49") (name "5V") (class "Default")
      (node (ref "C31") (pin "2") (pintype "passive"))
      (node (ref "D5") (pin "1") (pinfunction "A_1") (pintype "passive"))
      (node (ref "J5") (pin "4") (pinfunction "4_4") (pintype "passive"))
      (node (ref "REG1") (pin "3") (pinfunction "IN_3") (pintype "power_in"))
    )
    (net (code "50") (name "GND") (class "Default")
      (node (ref "ANT1") (pin "2") (pinfunction "GND_2") (pintype "power_in"))
      (node (ref "ANT1") (pin "3") (pinfunction "GND_3") (pintype "power_in"))
      (node (ref "ANT1") (pin "4") (pinfunction "GND_4") (pintype "power_in"))
      (node (ref "ANT1") (pin "5") (pinfunction "GND_5") (pintype "power_in"))
      (node (ref "ANT2") (pin "2") (pinfunction "GND_2") (pintype "power_in"))
      (node (ref "ANT2") (pin "3") (pinfunction "GND_3") (pintype "power_in"))
      (node (ref "ANT2") (pin "4") (pinfunction "GND_4") (pintype "power_in"))
      (node (ref "ANT2") (pin "5") (pinfunction "GND_5") (pintype "power_in"))
      (node (ref "ANT3") (pin "2") (pinfunction "GND_2") (pintype "power_in"))
      (node (ref "ANT3") (pin "3") (pinfunction "GND_3") (pintype "power_in"))
      (node (ref "ANT3") (pin "4") (pinfunction "GND_4") (pintype "power_in"))
      (node (ref "ANT3") (pin "5") (pinfunction "GND_5") (pintype "power_in"))
      (node (ref "C1") (pin "2") (pintype "passive"))
      (node (ref "C10") (pin "2") (pintype "passive"))
      (node (ref "C11") (pin "2") (pintype "passive"))
      (node (ref "C12") (pin "2") (pintype "passive"))
      (node (ref "C13") (pin "2") (pintype "passive"))
      (node (ref "C14") (pin "2") (pintype "passive"))
      (node (ref "C15") (pin "2") (pinfunction "2_2") (pintype "passive"))
      (node (ref "C16") (pin "2") (pintype "passive"))
      (node (ref "C17") (pin "2") (pintype "passive"))
      (node (ref "C18") (pin "2") (pintype "passive"))
      (node (ref "C19") (pin "2") (pintype "passive"))
      (node (ref "C2") (pin "2") (pintype "passive"))
      (node (ref "C20") (pin "1") (pintype "passive"))
      (node (ref "C21") (pin "1") (pintype "passive"))
      (node (ref "C25") (pin "2") (pintype "passive"))
      (node (ref "C26") (pin "2") (pintype "passive"))
      (node (ref "C27") (pin "2") (pinfunction "2_2") (pintype "passive"))
      (node (ref "C28") (pin "2") (pintype "passive"))
      (node (ref "C29") (pin "2") (pintype "passive"))
      (node (ref "C3") (pin "2") (pintype "passive"))
      (node (ref "C30") (pin "2") (pinfunction "2_2") (pintype "passive"))
      (node (ref "C31") (pin "1") (pintype "passive"))
      (node (ref "C32") (pin "1") (pintype "passive"))
      (node (ref "C33") (pin "2") (pinfunction "2_2") (pintype "passive"))
      (node (ref "C34") (pin "2") (pinfunction "-_2") (pintype "passive"))
      (node (ref "C35") (pin "2") (pinfunction "-_2") (pintype "passive"))
      (node (ref "C36") (pin "2") (pinfunction "2_2") (pintype "passive"))
      (node (ref "C4") (pin "2") (pintype "passive"))
      (node (ref "C5") (pin "2") (pintype "passive"))
      (node (ref "C6") (pin "2") (pintype "passive"))
      (node (ref "C7") (pin "2") (pintype "passive"))
      (node (ref "C8") (pin "2") (pintype "passive"))
      (node (ref "C9") (pin "2") (pintype "passive"))
      (node (ref "D1") (pin "2") (pinfunction "GND_2") (pintype "power_in"))
      (node (ref "D2") (pin "2") (pinfunction "GND_2") (pintype "power_in"))
      (node (ref "D3") (pin "2") (pinfunction "GND_2") (pintype "power_in"))
      (node (ref "D7") (pin "1") (pinfunction "A_1") (pintype "passive"))
      (node (ref "J1") (pin "G1") (pinfunction "GND_2_G1") (pintype "power_in"))
      (node (ref "J1") (pin "G2") (pinfunction "GND_2_G2") (pintype "power_in"))
      (node (ref "J1") (pin "G3") (pinfunction "GND_2_G3") (pintype "power_in"))
      (node (ref "J1") (pin "G4") (pinfunction "GND_2_G4") (pintype "power_in"))
      (node (ref "J1") (pin "G5") (pinfunction "GND_2_G5") (pintype "power_in"))
      (node (ref "J1") (pin "G6") (pinfunction "GND_2_G6") (pintype "power_in"))
      (node (ref "J1") (pin "G7") (pinfunction "GND_2_G7") (pintype "power_in"))
      (node (ref "J1") (pin "G8") (pinfunction "GND_2_G8") (pintype "power_in"))
      (node (ref "J1") (pin "S5_C4") (pinfunction "GND_1_S5_C4") (pintype "power_in"))
      (node (ref "J1") (pin "S6_C5") (pinfunction "VPP_S6_C5") (pintype "bidirectional"))
      (node (ref "J1") (pin "T6") (pinfunction "VSS/GND_T6") (pintype "power_in"))
      (node (ref "J4") (pin "4") (pinfunction "4_4") (pintype "passive"))
      (node (ref "J5") (pin "5") (pinfunction "5_5") (pintype "passive"))
      (node (ref "J6") (pin "3") (pinfunction "3_3") (pintype "passive"))
      (node (ref "J7") (pin "3") (pinfunction "3_3") (pintype "passive"))
      (node (ref "J8") (pin "3") (pinfunction "3_3") (pintype "passive"))
      (node (ref "J9") (pin "2") (pinfunction "2_2") (pintype "passive"))
      (node (ref "Q1") (pin "1") (pinfunction "E_1") (pintype "passive"))
      (node (ref "Q2") (pin "1") (pinfunction "E_1") (pintype "passive"))
      (node (ref "Q3") (pin "1") (pinfunction "E_1") (pintype "passive"))
      (node (ref "Q5") (pin "1") (pinfunction "E_1") (pintype "passive"))
      (node (ref "Q6") (pin "2") (pinfunction "E_2") (pintype "passive"))
      (node (ref "R15") (pin "2") (pinfunction "2_2") (pintype "passive"))
      (node (ref "R16") (pin "2") (pinfunction "2_2") (pintype "passive"))
      (node (ref "R17") (pin "2") (pinfunction "2_2") (pintype "passive"))
      (node (ref "R23") (pin "2") (pinfunction "2_2") (pintype "passive"))
      (node (ref "R24") (pin "2") (pinfunction "2_2") (pintype "passive"))
      (node (ref "R25") (pin "1") (pinfunction "1_1") (pintype "passive"))
      (node (ref "REG1") (pin "1") (pinfunction "GND_1") (pintype "power_in"))
      (node (ref "U1") (pin "4") (pinfunction "GND_4") (pintype "passive"))
      (node (ref "U2") (pin "14") (pinfunction "GND_14") (pintype "passive"))
      (node (ref "U2") (pin "16") (pinfunction "SIM_GND_16") (pintype "passive"))
      (node (ref "U2") (pin "27") (pinfunction "GND_27") (pintype "passive"))
      (node (ref "U2") (pin "31") (pinfunction "GND_31") (pintype "passive"))
      (node (ref "U2") (pin "40") (pinfunction "GND_40") (pintype "passive"))
      (node (ref "U2") (pin "42") (pinfunction "GND_42") (pintype "passive"))
      (node (ref "U2") (pin "44") (pinfunction "GND_44") (pintype "passive"))
      (node (ref "U2") (pin "45") (pinfunction "GND_45") (pintype "passive"))
      (node (ref "U2") (pin "48") (pinfunction "GND_48") (pintype "passive"))
      (node (ref "U2") (pin "49") (pinfunction "GND_49") (pintype "passive"))
      (node (ref "U2") (pin "53") (pinfunction "LOUD_SPKN_53") (pintype "passive"))
    )
    (net (code "51") (name "Net-(ANT1-Signal)") (class "Default")
      (node (ref "ANT1") (pin "1") (pinfunction "Signal_1") (pintype "input"))
      (node (ref "C14") (pin "1") (pintype "passive"))
      (node (ref "R9") (pin "2") (pinfunction "2_2") (pintype "passive"))
    )
    (net (code "52") (name "Net-(ANT2-Signal)") (class "Default")
      (node (ref "ANT2") (pin "1") (pinfunction "Signal_1") (pintype "input"))
      (node (ref "C17") (pin "1") (pintype "passive"))
      (node (ref "R14") (pin "2") (pinfunction "2_2") (pintype "passive"))
    )
    (net (code "53") (name "Net-(ANT3-Signal)") (class "Default")
      (node (ref "ANT3") (pin "1") (pinfunction "Signal_1") (pintype "input"))
      (node (ref "C19") (pin "1") (pintype "passive"))
      (node (ref "R19") (pin "2") (pinfunction "2_2") (pintype "passive"))
    )
    (net (code "54") (name "Net-(D4-K)") (class "Default")
      (node (ref "C15") (pin "1") (pinfunction "1_1") (pintype "passive"))
      (node (ref "D4") (pin "2") (pinfunction "K_2") (pintype "passive"))
      (node (ref "U2") (pin "52") (pinfunction "VRTC_52") (pintype "passive"))
    )
    (net (code "55") (name "Net-(D5-K)") (class "Default")
      (node (ref "D5") (pin "2") (pinfunction "K_2") (pintype "passive"))
      (node (ref "D6") (pin "1") (pinfunction "A_1") (pintype "passive"))
    )
    (net (code "56") (name "Net-(J1B-CARD_DETECTOR)") (class "Default")
      (node (ref "J1") (pin "S/W") (pinfunction "CARD_DETECTOR_S/W") (pintype "passive"))
      (node (ref "J2") (pin "1") (pinfunction "1_1") (pintype "passive"))
      (node (ref "R4") (pin "1") (pinfunction "1_1") (pintype "passive"))
    )
    (net (code "57") (name "Net-(J1B-CD{slash}DAT3)") (class "Default")
      (node (ref "J1") (pin "T2") (pinfunction "CD/DAT3_T2") (pintype "bidirectional"))
      (node (ref "R1") (pin "1") (pinfunction "1_1") (pintype "passive"))
    )
    (net (code "58") (name "Net-(J1B-DAT1)") (class "Default")
      (node (ref "J1") (pin "T8") (pinfunction "DAT1_T8") (pintype "bidirectional"))
      (node (ref "R3") (pin "1") (pinfunction "1_1") (pintype "passive"))
    )
    (net (code "59") (name "Net-(J1B-DAT2)") (class "Default")
      (node (ref "J1") (pin "T1") (pinfunction "DAT2_T1") (pintype "bidirectional"))
      (node (ref "R2") (pin "1") (pinfunction "1_1") (pintype "passive"))
    )
    (net (code "60") (name "Net-(L1-Pad1)") (class "Default")
      (node (ref "L1") (pin "1") (pinfunction "1_1") (pintype "passive"))
      (node (ref "R8") (pin "1") (pinfunction "1_1") (pintype "passive"))
    )
    (net (code "61") (name "Net-(LED1-K)") (class "Default")
      (node (ref "LED1") (pin "2") (pinfunction "K_2") (pintype "passive"))
      (node (ref "R10") (pin "4") (pinfunction "4_4") (pintype "passive"))
    )
    (net (code "62") (name "Net-(LED2-K)") (class "Default")
      (node (ref "LED2") (pin "2") (pinfunction "K_2") (pintype "passive"))
      (node (ref "R10") (pin "2") (pinfunction "2_2") (pintype "passive"))
    )
    (net (code "63") (name "Net-(LED3-K)") (class "Default")
      (node (ref "LED3") (pin "2") (pinfunction "K_2") (pintype "passive"))
      (node (ref "R10") (pin "1") (pinfunction "1_1") (pintype "passive"))
    )
    (net (code "64") (name "Net-(LED4-K)") (class "Default")
      (node (ref "LED4") (pin "2") (pinfunction "K_2") (pintype "passive"))
      (node (ref "R25") (pin "2") (pinfunction "2_2") (pintype "passive"))
    )
    (net (code "65") (name "Net-(Q1-B)") (class "Default")
      (node (ref "Q1") (pin "2") (pinfunction "B_2") (pintype "passive"))
      (node (ref "R11") (pin "2") (pinfunction "2_2") (pintype "passive"))
      (node (ref "R15") (pin "1") (pinfunction "1_1") (pintype "passive"))
    )
    (net (code "66") (name "Net-(Q1-C)") (class "Default")
      (node (ref "J3") (pin "1") (pinfunction "1_1") (pintype "passive"))
      (node (ref "Q1") (pin "3") (pinfunction "C_3") (pintype "passive"))
      (node (ref "R10") (pin "5") (pinfunction "5_5") (pintype "passive"))
    )
    (net (code "67") (name "Net-(Q2-B)") (class "Default")
      (node (ref "Q2") (pin "2") (pinfunction "B_2") (pintype "passive"))
      (node (ref "R12") (pin "2") (pinfunction "2_2") (pintype "passive"))
      (node (ref "R16") (pin "1") (pinfunction "1_1") (pintype "passive"))
    )
    (net (code "68") (name "Net-(Q2-C)") (class "Default")
      (node (ref "Q2") (pin "3") (pinfunction "C_3") (pintype "passive"))
      (node (ref "R10") (pin "7") (pinfunction "7_7") (pintype "passive"))
    )
    (net (code "69") (name "Net-(Q3-B)") (class "Default")
      (node (ref "Q3") (pin "2") (pinfunction "B_2") (pintype "passive"))
      (node (ref "R13") (pin "2") (pinfunction "2_2") (pintype "passive"))
      (node (ref "R17") (pin "1") (pinfunction "1_1") (pintype "passive"))
    )
    (net (code "70") (name "Net-(Q3-C)") (class "Default")
      (node (ref "Q3") (pin "3") (pinfunction "C_3") (pintype "passive"))
      (node (ref "R10") (pin "8") (pinfunction "8_8") (pintype "passive"))
    )
    (net (code "71") (name "Net-(Q4-G)") (class "Default")
      (node (ref "Q4") (pin "1") (pinfunction "G_1") (pintype "passive"))
      (node (ref "Q6") (pin "3") (pinfunction "C_3") (pintype "passive"))
      (node (ref "R18") (pin "1") (pinfunction "1_1") (pintype "passive"))
    )
    (net (code "72") (name "Net-(Q5-B)") (class "Default")
      (node (ref "Q5") (pin "2") (pinfunction "B_2") (pintype "passive"))
      (node (ref "R21") (pin "2") (pinfunction "2_2") (pintype "passive"))
      (node (ref "R23") (pin "1") (pinfunction "1_1") (pintype "passive"))
    )
    (net (code "73") (name "Net-(Q6-B)") (class "Default")
      (node (ref "Q6") (pin "1") (pinfunction "B_1") (pintype "passive"))
      (node (ref "R22") (pin "1") (pinfunction "1_1") (pintype "passive"))
      (node (ref "R24") (pin "1") (pinfunction "1_1") (pintype "passive"))
    )
    (net (code "74") (name "Net-(SW1-P3)") (class "Default")
      (node (ref "R20") (pin "2") (pinfunction "2_2") (pintype "passive"))
      (node (ref "R21") (pin "1") (pinfunction "1_1") (pintype "passive"))
      (node (ref "SW1") (pin "2") (pinfunction "P3_2") (pintype "passive"))
    )
    (net (code "75") (name "V_GNSS") (class "Default")
      (node (ref "C34") (pin "1") (pinfunction "+_1") (pintype "passive"))
      (node (ref "C35") (pin "1") (pinfunction "+_1") (pintype "passive"))
      (node (ref "Q4") (pin "3") (pinfunction "D_3") (pintype "passive"))
      (node (ref "R8") (pin "2") (pinfunction "2_2") (pintype "passive"))
      (node (ref "U2") (pin "26") (pinfunction "GNSS_VCC_26") (pintype "passive"))
    )
    (net (code "76") (name "unconnected-(D1-I{slash}O4-Pad6)") (class "Default")
      (node (ref "D1") (pin "6") (pinfunction "I/O4_6") (pintype "bidirectional"))
    )
    (net (code "77") (name "unconnected-(D2-I{slash}O1-Pad1)") (class "Default")
      (node (ref "D2") (pin "1") (pinfunction "I/O1_1") (pintype "bidirectional"))
    )
    (net (code "78") (name "unconnected-(D3-I{slash}O2-Pad3)") (class "Default")
      (node (ref "D3") (pin "3") (pinfunction "I/O2_3") (pintype "bidirectional"))
    )
    (net (code "79") (name "unconnected-(J1A-RSVD4-PadS4)") (class "Default")
      (node (ref "J1") (pin "S4") (pinfunction "RSVD4_S4") (pintype "passive"))
    )
    (net (code "80") (name "unconnected-(J1A-RSVD8-PadS8)") (class "Default")
      (node (ref "J1") (pin "S8") (pinfunction "RSVD8_S8") (pintype "passive"))
    )
    (net (code "81") (name "unconnected-(R6-Pad4)") (class "Default")
      (node (ref "R6") (pin "4") (pinfunction "4_4") (pintype "passive"))
    )
    (net (code "82") (name "unconnected-(R6-Pad5)") (class "Default")
      (node (ref "R6") (pin "5") (pinfunction "5_5") (pintype "passive"))
    )
    (net (code "83") (name "unconnected-(R10-Pad3)") (class "Default")
      (node (ref "R10") (pin "3") (pinfunction "3_3") (pintype "passive"))
    )
    (net (code "84") (name "unconnected-(R10-Pad6)") (class "Default")
      (node (ref "R10") (pin "6") (pinfunction "6_6") (pintype "passive"))
    )
    (net (code "85") (name "unconnected-(U1-NC-Pad5)") (class "Default")
      (node (ref "U1") (pin "5") (pinfunction "NC_5") (pintype "passive+no_connect"))
    )
    (net (code "86") (name "unconnected-(U2-PCM_CLK-Pad59)") (class "Default")
      (node (ref "U2") (pin "59") (pinfunction "PCM_CLK_59") (pintype "passive+no_connect"))
    )
    (net (code "87") (name "unconnected-(U2-PCM_IN-Pad62)") (class "Default")
      (node (ref "U2") (pin "62") (pinfunction "PCM_IN_62") (pintype "passive+no_connect"))
    )
    (net (code "88") (name "unconnected-(U2-PCM_OUT-Pad60)") (class "Default")
      (node (ref "U2") (pin "60") (pinfunction "PCM_OUT_60") (pintype "passive+no_connect"))
    )
    (net (code "89") (name "unconnected-(U2-PCM_SYNC-Pad61)") (class "Default")
      (node (ref "U2") (pin "61") (pinfunction "PCM_SYNC_61") (pintype "passive+no_connect"))
    )
    (net (code "90") (name "unconnected-(U2-RESERVED-Pad46)") (class "Default")
      (node (ref "U2") (pin "46") (pinfunction "RESERVED_46") (pintype "passive+no_connect"))
    )
    (net (code "91") (name "unconnected-(U2-SPKN-Pad4)") (class "Default")
      (node (ref "U2") (pin "4") (pinfunction "SPKN_4") (pintype "passive+no_connect"))
    )
    (net (code "92") (name "unconnected-(U2-SPKP-Pad3)") (class "Default")
      (node (ref "U2") (pin "3") (pinfunction "SPKP_3") (pintype "passive+no_connect"))
    )
    (net (code "93") (name "unconnected-(U2-VDD_EXT-Pad43)") (class "Default")
      (node (ref "U2") (pin "43") (pinfunction "VDD_EXT_43") (pintype "passive+no_connect"))
    )
  )
)
